# AX5243_schema.net
KiCad netlist of a schematic drawn in Altium Designer
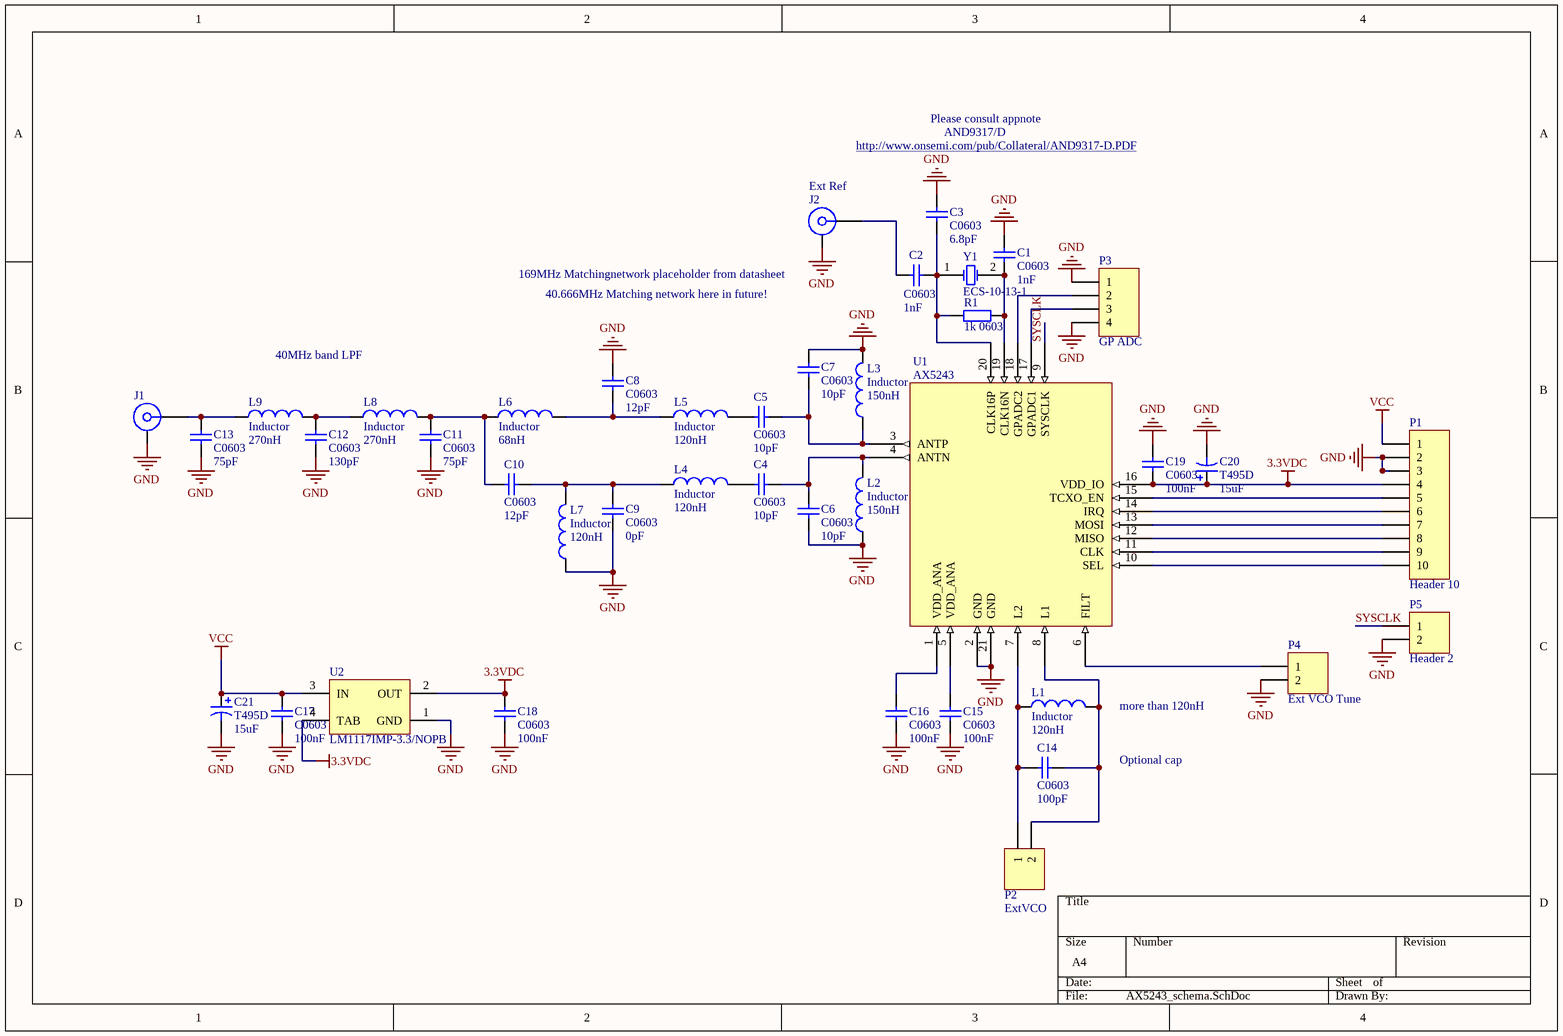
[diagram p0: AX5243_schema.SchDoc]

(export (version "E")
  (design (tool "Eeschema 10.0.6"))
  (components
    (comp (ref "C1")
      (value "C0603")
      (footprint "0603")
      (description "Ceramic Chip Capacitor - Standard")
      (fields (field (name "ALTIUM_VALUE") "1nF") (field (name "PUBLISHER") "Altium Limited"))
      (libsource (lib "KEMET Chip Capacitor") (part "C0603"))
    )
    (comp (ref "C2")
      (value "C0603")
      (footprint "0603")
      (description "Ceramic Chip Capacitor - Standard")
      (fields (field (name "ALTIUM_VALUE") "1nF") (field (name "PUBLISHER") "Altium Limited"))
      (libsource (lib "KEMET Chip Capacitor") (part "C0603"))
    )
    (comp (ref "C3")
      (value "C0603")
      (footprint "0603")
      (description "Ceramic Chip Capacitor - Standard")
      (fields (field (name "ALTIUM_VALUE") "6.8pF") (field (name "PUBLISHER") "Altium Limited"))
      (libsource (lib "KEMET Chip Capacitor") (part "C0603"))
    )
    (comp (ref "C4")
      (value "C0603")
      (footprint "0603")
      (description "Ceramic Chip Capacitor - Standard")
      (fields (field (name "ALTIUM_VALUE") "10pF") (field (name "PUBLISHER") "Altium Limited"))
      (libsource (lib "KEMET Chip Capacitor") (part "C0603"))
    )
    (comp (ref "C5")
      (value "C0603")
      (footprint "0603")
      (description "Ceramic Chip Capacitor - Standard")
      (fields (field (name "ALTIUM_VALUE") "10pF") (field (name "PUBLISHER") "Altium Limited"))
      (libsource (lib "KEMET Chip Capacitor") (part "C0603"))
    )
    (comp (ref "C6")
      (value "C0603")
      (footprint "0603")
      (description "Ceramic Chip Capacitor - Standard")
      (fields (field (name "ALTIUM_VALUE") "10pF") (field (name "PUBLISHER") "Altium Limited"))
      (libsource (lib "KEMET Chip Capacitor") (part "C0603"))
    )
    (comp (ref "C7")
      (value "C0603")
      (footprint "0603")
      (description "Ceramic Chip Capacitor - Standard")
      (fields (field (name "ALTIUM_VALUE") "10pF") (field (name "PUBLISHER") "Altium Limited"))
      (libsource (lib "KEMET Chip Capacitor") (part "C0603"))
    )
    (comp (ref "C8")
      (value "C0603")
      (footprint "0603")
      (description "Ceramic Chip Capacitor - Standard")
      (fields (field (name "ALTIUM_VALUE") "12pF") (field (name "PUBLISHER") "Altium Limited"))
      (libsource (lib "KEMET Chip Capacitor") (part "C0603"))
    )
    (comp (ref "C9")
      (value "C0603")
      (footprint "0603")
      (description "Ceramic Chip Capacitor - Standard")
      (fields (field (name "ALTIUM_VALUE") "0pF") (field (name "PUBLISHER") "Altium Limited"))
      (libsource (lib "KEMET Chip Capacitor") (part "C0603"))
    )
    (comp (ref "C10")
      (value "C0603")
      (footprint "0603")
      (description "Ceramic Chip Capacitor - Standard")
      (fields (field (name "ALTIUM_VALUE") "12pF") (field (name "PUBLISHER") "Altium Limited"))
      (libsource (lib "KEMET Chip Capacitor") (part "C0603"))
    )
    (comp (ref "C11")
      (value "C0603")
      (footprint "0603")
      (description "Ceramic Chip Capacitor - Standard")
      (fields (field (name "ALTIUM_VALUE") "75pF") (field (name "PUBLISHER") "Altium Limited"))
      (libsource (lib "KEMET Chip Capacitor") (part "C0603"))
    )
    (comp (ref "C12")
      (value "C0603")
      (footprint "0603")
      (description "Ceramic Chip Capacitor - Standard")
      (fields (field (name "ALTIUM_VALUE") "130pF") (field (name "PUBLISHER") "Altium Limited"))
      (libsource (lib "KEMET Chip Capacitor") (part "C0603"))
    )
    (comp (ref "C13")
      (value "C0603")
      (footprint "0603")
      (description "Ceramic Chip Capacitor - Standard")
      (fields (field (name "ALTIUM_VALUE") "75pF") (field (name "PUBLISHER") "Altium Limited"))
      (libsource (lib "KEMET Chip Capacitor") (part "C0603"))
    )
    (comp (ref "C14")
      (value "C0603")
      (footprint "0603")
      (description "Ceramic Chip Capacitor - Standard")
      (fields (field (name "ALTIUM_VALUE") "100pF") (field (name "PUBLISHER") "Altium Limited"))
      (libsource (lib "KEMET Chip Capacitor") (part "C0603"))
    )
    (comp (ref "C15")
      (value "C0603")
      (footprint "0603")
      (description "Ceramic Chip Capacitor - Standard")
      (fields (field (name "ALTIUM_VALUE") "100nF") (field (name "PUBLISHER") "Altium Limited"))
      (libsource (lib "KEMET Chip Capacitor") (part "C0603"))
    )
    (comp (ref "C16")
      (value "C0603")
      (footprint "0603")
      (description "Ceramic Chip Capacitor - Standard")
      (fields (field (name "ALTIUM_VALUE") "100nF") (field (name "PUBLISHER") "Altium Limited"))
      (libsource (lib "KEMET Chip Capacitor") (part "C0603"))
    )
    (comp (ref "C17")
      (value "C0603")
      (footprint "0603")
      (description "Ceramic Chip Capacitor - Standard")
      (fields (field (name "ALTIUM_VALUE") "100nF") (field (name "PUBLISHER") "Altium Limited"))
      (libsource (lib "KEMET Chip Capacitor") (part "C0603"))
    )
    (comp (ref "C18")
      (value "C0603")
      (footprint "0603")
      (description "Ceramic Chip Capacitor - Standard")
      (fields (field (name "ALTIUM_VALUE") "100nF") (field (name "PUBLISHER") "Altium Limited"))
      (libsource (lib "KEMET Chip Capacitor") (part "C0603"))
    )
    (comp (ref "C19")
      (value "C0603")
      (footprint "0603")
      (description "Ceramic Chip Capacitor - Standard")
      (fields (field (name "ALTIUM_VALUE") "100nF") (field (name "PUBLISHER") "Altium Limited"))
      (libsource (lib "KEMET Chip Capacitor") (part "C0603"))
    )
    (comp (ref "C20")
      (value "T495D")
      (footprint "D")
      (description "Solid Tantalum Chip Capacitor, Standard T495 Series - Low ESR, Surge Robust")
      (fields (field (name "ALTIUM_VALUE") "15uF") (field (name "PUBLISHER") "Altium Limited"))
      (libsource (lib "KEMET Chip Capacitor") (part "T495D"))
    )
    (comp (ref "C21")
      (value "T495D")
      (footprint "D")
      (description "Solid Tantalum Chip Capacitor, Standard T495 Series - Low ESR, Surge Robust")
      (fields (field (name "ALTIUM_VALUE") "15uF") (field (name "PUBLISHER") "Altium Limited"))
      (libsource (lib "KEMET Chip Capacitor") (part "T495D"))
    )
    (comp (ref "J1")
      (value "32K145-400L5")
      (footprint "ROS-32K145-400L5_V")
      (description "SMA Right Angle Jack, Edge Mount, Up to 18 GHz, -55 to 155 degC")
      (libsource (lib "Rosenberger SMA") (part "32K145-400L5"))
    )
    (comp (ref "J2")
      (value "32K10A-40ML5")
      (footprint "ROS-32K10A-40ML5_V")
      (description "SMA Straight Jack, Up to 12.4 GHz, -55 to 155 degC")
      (libsource (lib "Rosenberger SMA") (part "32K10A-40ML5"))
    )
    (comp (ref "L1")
      (value "Inductor")
      (footprint "INDC1608L")
      (fields (field (name "ALTIUM_VALUE") "120nH") (field (name "PUBLISHER") "Altium Limited"))
      (libsource (lib "Miscellaneous Devices") (part "Inductor"))
    )
    (comp (ref "L2")
      (value "Inductor")
      (footprint "INDC1608L")
      (fields (field (name "ALTIUM_VALUE") "150nH") (field (name "PUBLISHER") "Altium Limited"))
      (libsource (lib "Miscellaneous Devices") (part "Inductor"))
    )
    (comp (ref "L3")
      (value "Inductor")
      (footprint "INDC1608L")
      (fields (field (name "ALTIUM_VALUE") "150nH") (field (name "PUBLISHER") "Altium Limited"))
      (libsource (lib "Miscellaneous Devices") (part "Inductor"))
    )
    (comp (ref "L4")
      (value "Inductor")
      (footprint "INDC1608L")
      (fields (field (name "ALTIUM_VALUE") "120nH") (field (name "PUBLISHER") "Altium Limited"))
      (libsource (lib "Miscellaneous Devices") (part "Inductor"))
    )
    (comp (ref "L5")
      (value "Inductor")
      (footprint "INDC1608L")
      (fields (field (name "ALTIUM_VALUE") "120nH") (field (name "PUBLISHER") "Altium Limited"))
      (libsource (lib "Miscellaneous Devices") (part "Inductor"))
    )
    (comp (ref "L6")
      (value "Inductor")
      (footprint "INDC1608L")
      (fields (field (name "ALTIUM_VALUE") "68nH") (field (name "PUBLISHER") "Altium Limited"))
      (libsource (lib "Miscellaneous Devices") (part "Inductor"))
    )
    (comp (ref "L7")
      (value "Inductor")
      (footprint "INDC1608L")
      (fields (field (name "ALTIUM_VALUE") "120nH") (field (name "PUBLISHER") "Altium Limited"))
      (libsource (lib "Miscellaneous Devices") (part "Inductor"))
    )
    (comp (ref "L8")
      (value "Inductor")
      (footprint "INDC1608L")
      (fields (field (name "ALTIUM_VALUE") "270nH") (field (name "PUBLISHER") "Altium Limited"))
      (libsource (lib "Miscellaneous Devices") (part "Inductor"))
    )
    (comp (ref "L9")
      (value "Inductor")
      (footprint "INDC1608L")
      (fields (field (name "ALTIUM_VALUE") "270nH") (field (name "PUBLISHER") "Altium Limited"))
      (libsource (lib "Miscellaneous Devices") (part "Inductor"))
    )
    (comp (ref "P1")
      (value "Header 10")
      (footprint "HDR1X10")
      (description "Header, 10-Pin")
      (fields (field (name "PUBLISHER") "Altium Limited"))
      (libsource (lib "Miscellaneous Connectors") (part "Header 10"))
    )
    (comp (ref "P2")
      (value "ExtVCO")
      (footprint "HDR1X2")
      (description "Header, 2-Pin")
      (fields (field (name "PUBLISHER") "Altium Limited"))
      (libsource (lib "") (part "Header 2_1"))
    )
    (comp (ref "P3")
      (value "GP ADC")
      (footprint "HDR1X4")
      (description "Header, 4-Pin")
      (fields (field (name "PUBLISHER") "Altium Limited"))
      (libsource (lib "Miscellaneous Connectors") (part "Header 4"))
    )
    (comp (ref "P4")
      (value "Ext VCO Tune")
      (footprint "HDR1X2")
      (description "Header, 2-Pin")
      (fields (field (name "PUBLISHER") "Altium Limited"))
      (libsource (lib "Miscellaneous Connectors") (part "Header 2"))
    )
    (comp (ref "P5")
      (value "Header 2")
      (footprint "HDR1X2")
      (description "Header, 2-Pin")
      (fields (field (name "PUBLISHER") "Altium Limited"))
      (libsource (lib "Miscellaneous Connectors") (part "Header 2"))
    )
    (comp (ref "R1") (value "1k 0603") (footprint "R0603") (libsource (lib "ftg_lib") (part "1k 0603")))
    (comp (ref "U1")
      (value "AX5243")
      (footprint "QFN20 4,00x4,00mm ON Semi")
      (description "Data Tranceiver 27-1050MHz")
      (libsource (lib "ftg_lib") (part "AX5243"))
    )
    (comp (ref "U2")
      (value "LM1117IMP-3.3/NOPB")
      (footprint "MP04A_N")
      (description "800mA Low-Dropout Linear Regulator, 4-pin SOT-223, Pb-Free")
      (fields (field (name "MANUFACTURER") "National Semiconductor"))
      (libsource (lib "National Semiconductor LDO") (part "LM1117IMP-3.3/NOPB"))
    )
    (comp (ref "Y1")
      (value "ECS-10-13-1")
      (footprint "HC-49U")
      (description "Crystal Oscillator")
      (fields (field (name "PUBLISHER") "Altium Limited"))
      (libsource (lib "ECS Crystal Oscillator") (part "ECS-10-13-1"))
    )
  )
  (nets
    (net (code "1") (name "/SYSCLK") (class "Default")
      (node (ref "P5") (pin "1") (pinfunction "1_1") (pintype "passive"))
      (node (ref "U1") (pin "9") (pinfunction "SYSCLK_9") (pintype "input"))
    )
    (net (code "2") (name "3.3VDC") (class "Default")
      (node (ref "C18") (pin "2") (pinfunction "2_2") (pintype "passive"))
      (node (ref "C19") (pin "1") (pinfunction "1_1") (pintype "passive"))
      (node (ref "C20") (pin "1") (pinfunction "1_1") (pintype "passive"))
      (node (ref "P1") (pin "4") (pinfunction "4_4") (pintype "passive"))
      (node (ref "U1") (pin "16") (pinfunction "VDD_IO_16") (pintype "input"))
      (node (ref "U2") (pin "2") (pinfunction "OUT_2") (pintype "power_in"))
      (node (ref "U2") (pin "4") (pinfunction "TAB_4") (pintype "power_in"))
    )
    (net (code "3") (name "GND") (class "Default")
      (node (ref "C1") (pin "2") (pinfunction "2_2") (pintype "passive"))
      (node (ref "C11") (pin "1") (pinfunction "1_1") (pintype "passive"))
      (node (ref "C12") (pin "1") (pinfunction "1_1") (pintype "passive"))
      (node (ref "C13") (pin "1") (pinfunction "1_1") (pintype "passive"))
      (node (ref "C15") (pin "1") (pinfunction "1_1") (pintype "passive"))
      (node (ref "C16") (pin "1") (pinfunction "1_1") (pintype "passive"))
      (node (ref "C17") (pin "1") (pinfunction "1_1") (pintype "passive"))
      (node (ref "C18") (pin "1") (pinfunction "1_1") (pintype "passive"))
      (node (ref "C19") (pin "2") (pinfunction "2_2") (pintype "passive"))
      (node (ref "C20") (pin "2") (pinfunction "2_2") (pintype "passive"))
      (node (ref "C21") (pin "2") (pinfunction "2_2") (pintype "passive"))
      (node (ref "C3") (pin "2") (pinfunction "2_2") (pintype "passive"))
      (node (ref "C6") (pin "1") (pinfunction "1_1") (pintype "passive"))
      (node (ref "C7") (pin "2") (pinfunction "2_2") (pintype "passive"))
      (node (ref "C8") (pin "1") (pinfunction "1_1") (pintype "passive"))
      (node (ref "C9") (pin "2") (pinfunction "2_2") (pintype "passive"))
      (node (ref "J1") (pin "MP") (pinfunction "MP_MP") (pintype "passive"))
      (node (ref "J2") (pin "MP") (pinfunction "MP_MP") (pintype "passive"))
      (node (ref "L2") (pin "1") (pinfunction "1_1") (pintype "passive"))
      (node (ref "L3") (pin "2") (pinfunction "2_2") (pintype "passive"))
      (node (ref "L7") (pin "1") (pinfunction "1_1") (pintype "passive"))
      (node (ref "P1") (pin "2") (pinfunction "2_2") (pintype "passive"))
      (node (ref "P1") (pin "3") (pinfunction "3_3") (pintype "passive"))
      (node (ref "P3") (pin "1") (pinfunction "1_1") (pintype "passive"))
      (node (ref "P3") (pin "4") (pinfunction "4_4") (pintype "passive"))
      (node (ref "P4") (pin "2") (pinfunction "2_2") (pintype "passive"))
      (node (ref "P5") (pin "2") (pinfunction "2_2") (pintype "passive"))
      (node (ref "U1") (pin "2") (pinfunction "GND_2") (pintype "input"))
      (node (ref "U1") (pin "21") (pinfunction "GND_21") (pintype "input"))
      (node (ref "U2") (pin "1") (pinfunction "GND_1") (pintype "power_in"))
    )
    (net (code "4") (name "Net-(C2-Pad2)") (class "Default")
      (node (ref "C2") (pin "2") (pinfunction "2_2") (pintype "passive"))
      (node (ref "J2") (pin "1") (pinfunction "1_1") (pintype "passive"))
    )
    (net (code "5") (name "Net-(C4-Pad1)") (class "Default")
      (node (ref "C4") (pin "1") (pinfunction "1_1") (pintype "passive"))
      (node (ref "L4") (pin "2") (pinfunction "2_2") (pintype "passive"))
    )
    (net (code "6") (name "Net-(C5-Pad1)") (class "Default")
      (node (ref "C5") (pin "1") (pinfunction "1_1") (pintype "passive"))
      (node (ref "L5") (pin "2") (pinfunction "2_2") (pintype "passive"))
    )
    (net (code "7") (name "Net-(C8-Pad2)") (class "Default")
      (node (ref "C8") (pin "2") (pinfunction "2_2") (pintype "passive"))
      (node (ref "L5") (pin "1") (pinfunction "1_1") (pintype "passive"))
      (node (ref "L6") (pin "2") (pinfunction "2_2") (pintype "passive"))
    )
    (net (code "8") (name "Net-(C10-Pad1)") (class "Default")
      (node (ref "C10") (pin "1") (pinfunction "1_1") (pintype "passive"))
      (node (ref "C11") (pin "2") (pinfunction "2_2") (pintype "passive"))
      (node (ref "L6") (pin "1") (pinfunction "1_1") (pintype "passive"))
      (node (ref "L8") (pin "2") (pinfunction "2_2") (pintype "passive"))
    )
    (net (code "9") (name "Net-(C10-Pad2)") (class "Default")
      (node (ref "C10") (pin "2") (pinfunction "2_2") (pintype "passive"))
      (node (ref "C9") (pin "1") (pinfunction "1_1") (pintype "passive"))
      (node (ref "L4") (pin "1") (pinfunction "1_1") (pintype "passive"))
      (node (ref "L7") (pin "2") (pinfunction "2_2") (pintype "passive"))
    )
    (net (code "10") (name "Net-(C12-Pad2)") (class "Default")
      (node (ref "C12") (pin "2") (pinfunction "2_2") (pintype "passive"))
      (node (ref "L8") (pin "1") (pinfunction "1_1") (pintype "passive"))
      (node (ref "L9") (pin "2") (pinfunction "2_2") (pintype "passive"))
    )
    (net (code "11") (name "Net-(C13-Pad2)") (class "Default")
      (node (ref "C13") (pin "2") (pinfunction "2_2") (pintype "passive"))
      (node (ref "J1") (pin "1") (pinfunction "1_1") (pintype "passive"))
      (node (ref "L9") (pin "1") (pinfunction "1_1") (pintype "passive"))
    )
    (net (code "12") (name "Net-(C15-Pad2)") (class "Default")
      (node (ref "C15") (pin "2") (pinfunction "2_2") (pintype "passive"))
      (node (ref "U1") (pin "5") (pinfunction "VDD_ANA_5") (pintype "input"))
    )
    (net (code "13") (name "Net-(C16-Pad2)") (class "Default")
      (node (ref "C16") (pin "2") (pinfunction "2_2") (pintype "passive"))
      (node (ref "U1") (pin "1") (pinfunction "VDD_ANA_1") (pintype "input"))
    )
    (net (code "14") (name "Net-(U1-ANTN)") (class "Default")
      (node (ref "C4") (pin "2") (pinfunction "2_2") (pintype "passive"))
      (node (ref "C6") (pin "2") (pinfunction "2_2") (pintype "passive"))
      (node (ref "L2") (pin "2") (pinfunction "2_2") (pintype "passive"))
      (node (ref "U1") (pin "4") (pinfunction "ANTN_4") (pintype "output"))
    )
    (net (code "15") (name "Net-(U1-ANTP)") (class "Default")
      (node (ref "C5") (pin "2") (pinfunction "2_2") (pintype "passive"))
      (node (ref "C7") (pin "1") (pinfunction "1_1") (pintype "passive"))
      (node (ref "L3") (pin "1") (pinfunction "1_1") (pintype "passive"))
      (node (ref "U1") (pin "3") (pinfunction "ANTP_3") (pintype "output"))
    )
    (net (code "16") (name "Net-(U1-CLK)") (class "Default")
      (node (ref "P1") (pin "9") (pinfunction "9_9") (pintype "passive"))
      (node (ref "U1") (pin "11") (pinfunction "CLK_11") (pintype "input"))
    )
    (net (code "17") (name "Net-(U1-CLK16N)") (class "Default")
      (node (ref "C1") (pin "1") (pinfunction "1_1") (pintype "passive"))
      (node (ref "R1") (pin "2") (pinfunction "2_2") (pintype "passive"))
      (node (ref "U1") (pin "19") (pinfunction "CLK16N_19") (pintype "input"))
      (node (ref "Y1") (pin "2") (pinfunction "OSC2_2") (pintype "passive"))
    )
    (net (code "18") (name "Net-(U1-CLK16P)") (class "Default")
      (node (ref "C2") (pin "1") (pinfunction "1_1") (pintype "passive"))
      (node (ref "C3") (pin "1") (pinfunction "1_1") (pintype "passive"))
      (node (ref "R1") (pin "1") (pinfunction "1_1") (pintype "passive"))
      (node (ref "U1") (pin "20") (pinfunction "CLK16P_20") (pintype "input"))
      (node (ref "Y1") (pin "1") (pinfunction "OSC1_1") (pintype "passive"))
    )
    (net (code "19") (name "Net-(U1-FILT)") (class "Default")
      (node (ref "P4") (pin "1") (pinfunction "1_1") (pintype "passive"))
      (node (ref "U1") (pin "6") (pinfunction "FILT_6") (pintype "input"))
    )
    (net (code "20") (name "Net-(U1-GPADC1)") (class "Default")
      (node (ref "P3") (pin "3") (pinfunction "3_3") (pintype "passive"))
      (node (ref "U1") (pin "17") (pinfunction "GPADC1_17") (pintype "input"))
    )
    (net (code "21") (name "Net-(U1-GPADC2)") (class "Default")
      (node (ref "P3") (pin "2") (pinfunction "2_2") (pintype "passive"))
      (node (ref "U1") (pin "18") (pinfunction "GPADC2_18") (pintype "input"))
    )
    (net (code "22") (name "Net-(U1-IRQ)") (class "Default")
      (node (ref "P1") (pin "6") (pinfunction "6_6") (pintype "passive"))
      (node (ref "U1") (pin "14") (pinfunction "IRQ_14") (pintype "input"))
    )
    (net (code "23") (name "Net-(U1-L1)") (class "Default")
      (node (ref "C14") (pin "2") (pinfunction "2_2") (pintype "passive"))
      (node (ref "L1") (pin "2") (pinfunction "2_2") (pintype "passive"))
      (node (ref "P2") (pin "2") (pinfunction "2_2") (pintype "passive"))
      (node (ref "U1") (pin "8") (pinfunction "L1_8") (pintype "input"))
    )
    (net (code "24") (name "Net-(U1-L2)") (class "Default")
      (node (ref "C14") (pin "1") (pinfunction "1_1") (pintype "passive"))
      (node (ref "L1") (pin "1") (pinfunction "1_1") (pintype "passive"))
      (node (ref "P2") (pin "1") (pinfunction "1_1") (pintype "passive"))
      (node (ref "U1") (pin "7") (pinfunction "L2_7") (pintype "input"))
    )
    (net (code "25") (name "Net-(U1-MISO)") (class "Default")
      (node (ref "P1") (pin "8") (pinfunction "8_8") (pintype "passive"))
      (node (ref "U1") (pin "12") (pinfunction "MISO_12") (pintype "input"))
    )
    (net (code "26") (name "Net-(U1-MOSI)") (class "Default")
      (node (ref "P1") (pin "7") (pinfunction "7_7") (pintype "passive"))
      (node (ref "U1") (pin "13") (pinfunction "MOSI_13") (pintype "input"))
    )
    (net (code "27") (name "Net-(U1-SEL)") (class "Default")
      (node (ref "P1") (pin "10") (pinfunction "10_10") (pintype "passive"))
      (node (ref "U1") (pin "10") (pinfunction "SEL_10") (pintype "input"))
    )
    (net (code "28") (name "Net-(U1-TCXO_EN)") (class "Default")
      (node (ref "P1") (pin "5") (pinfunction "5_5") (pintype "passive"))
      (node (ref "U1") (pin "15") (pinfunction "TCXO_EN_15") (pintype "input"))
    )
    (net (code "29") (name "VCC") (class "Default")
      (node (ref "C17") (pin "2") (pinfunction "2_2") (pintype "passive"))
      (node (ref "C21") (pin "1") (pinfunction "1_1") (pintype "passive"))
      (node (ref "P1") (pin "1") (pinfunction "1_1") (pintype "passive"))
      (node (ref "U2") (pin "3") (pinfunction "IN_3") (pintype "power_in"))
    )
  )
)
